# fet_overdrive_v50.net
KiCad netlist of a schematic drawn in EAGLE
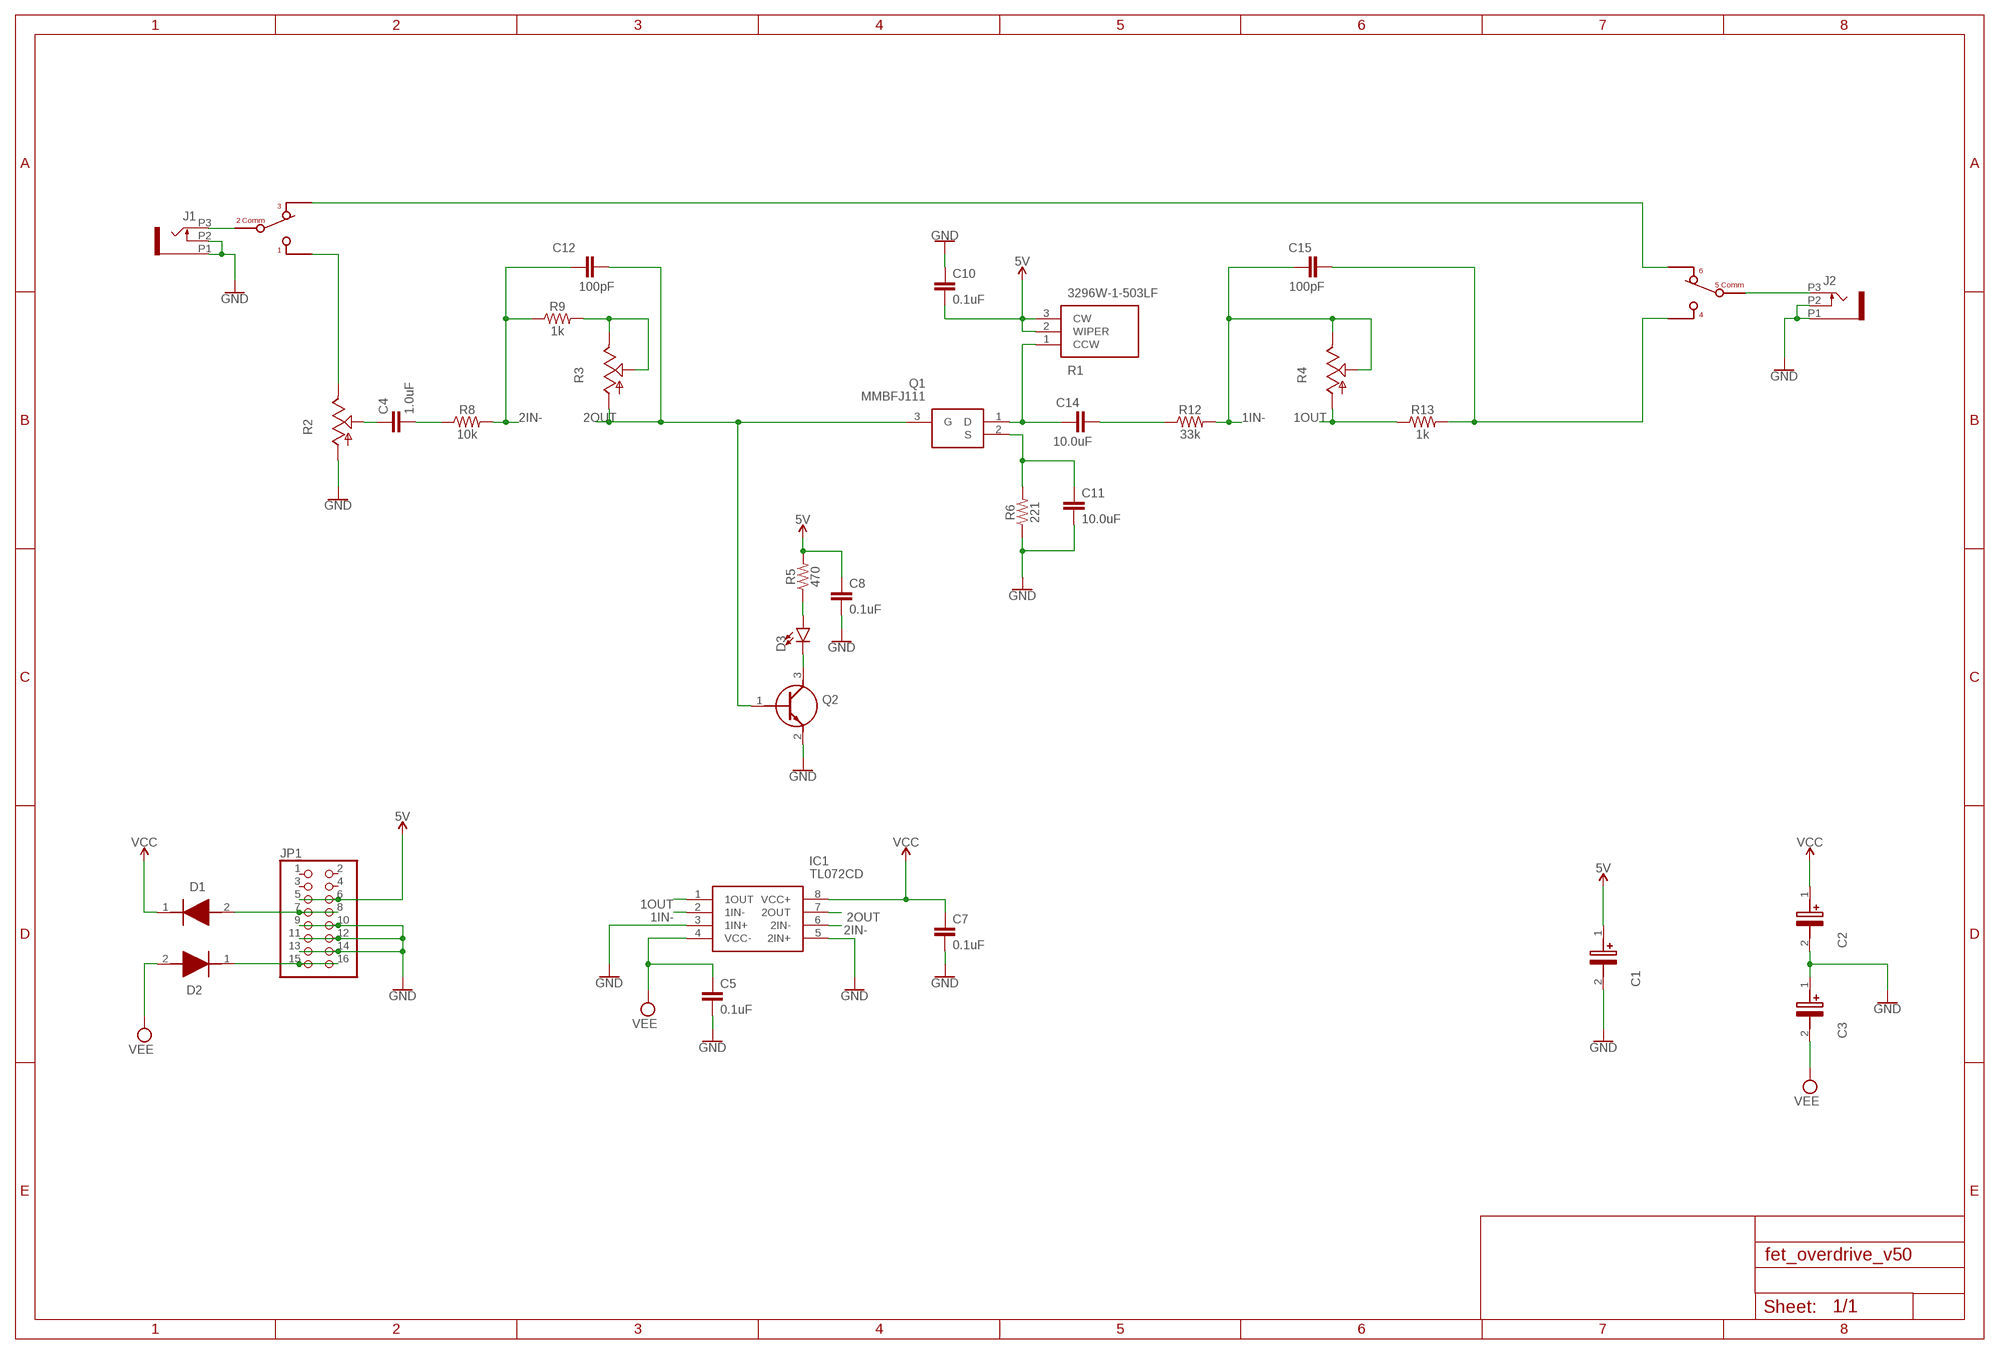
[diagram p0: schematic, sheet 1]

(export (version "E")
  (design (tool "Eeschema 10.0.6"))
  (components
    (comp (ref "C1")
      (value "EEE-FP1E220AR")
      (footprint "eagle-import:EEE0GA101SR")
      (fields (field (name "MOUSER_PART_NUMBER") "667-EEE-FP1E220AR"))
      (libsource (lib "eagle-import") (part "EEE-FP1E220AR"))
    )
    (comp (ref "C2")
      (value "EEE-FK1V470P")
      (footprint "eagle-import:EEE1AA101SP")
      (fields (field (name "MOUSER_PART_NUMBER") "667-EEE-FK1V470P"))
      (libsource (lib "eagle-import") (part "EEE-FK1V470P"))
    )
    (comp (ref "C3")
      (value "EEE-FK1V470P")
      (footprint "eagle-import:EEE1AA101SP")
      (fields (field (name "MOUSER_PART_NUMBER") "667-EEE-FK1V470P"))
      (libsource (lib "eagle-import") (part "EEE-FK1V470P"))
    )
    (comp (ref "C4")
      (value "1.0uF")
      (footprint "eagle-import:0603")
      (libsource (lib "eagle-import") (part "1.0UF-0603-16V-10%"))
    )
    (comp (ref "C5")
      (value "0.1uF")
      (footprint "eagle-import:0603")
      (libsource (lib "eagle-import") (part "0.1UF-0603-25V-5%"))
    )
    (comp (ref "C7")
      (value "0.1uF")
      (footprint "eagle-import:0603")
      (libsource (lib "eagle-import") (part "0.1UF-0603-25V-5%"))
    )
    (comp (ref "C8")
      (value "0.1uF")
      (footprint "eagle-import:0603")
      (libsource (lib "eagle-import") (part "0.1UF-0603-25V-5%"))
    )
    (comp (ref "C10")
      (value "0.1uF")
      (footprint "eagle-import:0603")
      (libsource (lib "eagle-import") (part "0.1UF-0603-25V-5%"))
    )
    (comp (ref "C11")
      (value "10.0uF")
      (footprint "eagle-import:0603")
      (libsource (lib "eagle-import") (part "1.0UF-0603-16V-10%"))
    )
    (comp (ref "C12")
      (value "100pF")
      (footprint "eagle-import:0603")
      (libsource (lib "eagle-import") (part "100PF-0603-50V-5%"))
    )
    (comp (ref "C14")
      (value "10.0uF")
      (footprint "eagle-import:0603")
      (libsource (lib "eagle-import") (part "1.0UF-0603-16V-10%"))
    )
    (comp (ref "C15")
      (value "100pF")
      (footprint "eagle-import:0603")
      (libsource (lib "eagle-import") (part "100PF-0603-50V-5%"))
    )
    (comp (ref "D1")
      (value "1N5819HW-7-F")
      (footprint "eagle-import:SOD3716X145N")
      (fields (field (name "MOUSER_PART_NUMBER") "621-1N5819HW-F"))
      (libsource (lib "eagle-import") (part "1N5819HW-7-F"))
    )
    (comp (ref "D2")
      (value "1N5819HW-7-F")
      (footprint "eagle-import:SOD3716X145N")
      (fields (field (name "MOUSER_PART_NUMBER") "621-1N5819HW-F"))
      (libsource (lib "eagle-import") (part "1N5819HW-7-F"))
    )
    (comp (ref "D3")
      (value "LED3MM")
      (footprint "eagle-import:LED_3MM")
      (libsource (lib "eagle-import") (part "LED3MM"))
    )
    (comp (ref "IC1")
      (value "TL072CD")
      (footprint "eagle-import:SOIC127P600X175-8N")
      (fields (field (name "MOUSER_PART_NUMBER") "595-TL072CD"))
      (libsource (lib "eagle-import") (part "TL072CD"))
    )
    (comp (ref "J1")
      (value "PJ301_THONKICONN6")
      (footprint "eagle-import:WQP_PJ_301M6")
      (libsource (lib "eagle-import") (part "PJ301_THONKICONN6"))
    )
    (comp (ref "J2")
      (value "PJ301_THONKICONN6")
      (footprint "eagle-import:WQP_PJ_301M6")
      (libsource (lib "eagle-import") (part "PJ301_THONKICONN6"))
    )
    (comp (ref "JP1")
      (value "PINHD-2X8")
      (footprint "eagle-import:2X08")
      (libsource (lib "eagle-import") (part "PINHD-2X8"))
    )
    (comp (ref "Q1")
      (value "MMBFJ111")
      (footprint "eagle-import:SOT96P237X111-3N")
      (fields (field (name "MOUSER_PART_NUMBER") "512-MMBFJ111"))
      (libsource (lib "eagle-import") (part "MMBFJ111"))
    )
    (comp (ref "Q2")
      (value "SMMBT3904LT1G")
      (footprint "eagle-import:SOT96P237X111-3N")
      (fields (field (name "MOUSER_PART_NUMBER") "863-SMMBT3904LT1G"))
      (libsource (lib "eagle-import") (part "SMMBT3904LT1G"))
    )
    (comp (ref "R1")
      (value "3296W-1-503LF")
      (footprint "eagle-import:3296W-1")
      (fields (field (name "MOUSER_PART_NUMBER") "652-3296W-1-503LF"))
      (libsource (lib "eagle-import") (part "3296W-1-503LF"))
    )
    (comp (ref "R2")
      (value "POT_USVERTICAL_PS")
      (footprint "eagle-import:ALPS_POT_VERTICAL_PS")
      (libsource (lib "eagle-import") (part "POT_USVERTICAL_PS"))
    )
    (comp (ref "R3")
      (value "POT_USVERTICAL_PS")
      (footprint "eagle-import:ALPS_POT_VERTICAL_PS")
      (libsource (lib "eagle-import") (part "POT_USVERTICAL_PS"))
    )
    (comp (ref "R4")
      (value "POT_USVERTICAL_PS")
      (footprint "eagle-import:ALPS_POT_VERTICAL_PS")
      (libsource (lib "eagle-import") (part "POT_USVERTICAL_PS"))
    )
    (comp (ref "R5")
      (value "470")
      (footprint "eagle-import:0603")
      (libsource (lib "eagle-import") (part "470OHM-0603-1/10W-1%"))
    )
    (comp (ref "R6")
      (value "221")
      (footprint "eagle-import:0603")
      (libsource (lib "eagle-import") (part "1KOHM-0603-1/10W-1%"))
    )
    (comp (ref "R8")
      (value "10k")
      (footprint "eagle-import:0603")
      (libsource (lib "eagle-import") (part "10KOHM-0603-1/10W-1%"))
    )
    (comp (ref "R9")
      (value "1k")
      (footprint "eagle-import:0603")
      (libsource (lib "eagle-import") (part "1KOHM-0603-1/10W-1%"))
    )
    (comp (ref "R12")
      (value "33k")
      (footprint "eagle-import:0603")
      (libsource (lib "eagle-import") (part "33KOHM-0603-1/10W-1%"))
    )
    (comp (ref "R13")
      (value "1k")
      (footprint "eagle-import:0603")
      (libsource (lib "eagle-import") (part "1KOHM-0603-1/10W-1%"))
    )
    (comp (ref "U$2")
      (value "DAILYWELL-DPDT")
      (footprint "eagle-import:DAILYWELL-DPDT")
      (libsource (lib "eagle-import") (part "DAILYWELL-DPDT"))
    )
  )
  (nets
    (net (code "1") (name "/1IN-") (class "Default")
      (node (ref "C15") (pin "1") (pinfunction "1_1") (pintype "passive"))
      (node (ref "IC1") (pin "2") (pinfunction "1IN-_2") (pintype "bidirectional"))
      (node (ref "R12") (pin "2") (pinfunction "2_2") (pintype "passive"))
      (node (ref "R4") (pin "P$1") (pinfunction "E_P$1") (pintype "passive"))
      (node (ref "R4") (pin "P$2") (pinfunction "S_P$2") (pintype "passive"))
    )
    (net (code "2") (name "/1OUT") (class "Default")
      (node (ref "IC1") (pin "1") (pinfunction "1OUT_1") (pintype "bidirectional"))
      (node (ref "R13") (pin "1") (pinfunction "1_1") (pintype "passive"))
      (node (ref "R4") (pin "P$3") (pinfunction "A_P$3") (pintype "passive"))
    )
    (net (code "3") (name "/2IN-") (class "Default")
      (node (ref "C12") (pin "1") (pinfunction "1_1") (pintype "passive"))
      (node (ref "IC1") (pin "6") (pinfunction "2IN-_6") (pintype "bidirectional"))
      (node (ref "R8") (pin "2") (pinfunction "2_2") (pintype "passive"))
      (node (ref "R9") (pin "1") (pinfunction "1_1") (pintype "passive"))
    )
    (net (code "4") (name "/2OUT") (class "Default")
      (node (ref "C12") (pin "2") (pinfunction "2_2") (pintype "passive"))
      (node (ref "IC1") (pin "7") (pinfunction "2OUT_7") (pintype "bidirectional"))
      (node (ref "Q1") (pin "3") (pinfunction "G_3") (pintype "bidirectional"))
      (node (ref "Q2") (pin "1") (pinfunction "B_1") (pintype "bidirectional"))
      (node (ref "R3") (pin "P$3") (pinfunction "A_P$3") (pintype "passive"))
    )
    (net (code "5") (name "5V") (class "Default")
      (node (ref "C1") (pin "1") (pinfunction "+_1") (pintype "bidirectional"))
      (node (ref "C10") (pin "2") (pinfunction "2_2") (pintype "passive"))
      (node (ref "C8") (pin "1") (pinfunction "1_1") (pintype "passive"))
      (node (ref "JP1") (pin "5") (pinfunction "5_5") (pintype "passive"))
      (node (ref "JP1") (pin "6") (pinfunction "6_6") (pintype "passive"))
      (node (ref "R1") (pin "2") (pinfunction "WIPER_2") (pintype "bidirectional"))
      (node (ref "R1") (pin "3") (pinfunction "CW_3") (pintype "bidirectional"))
      (node (ref "R5") (pin "2") (pinfunction "2_2") (pintype "passive"))
    )
    (net (code "6") (name "GND") (class "Default")
      (node (ref "C1") (pin "2") (pinfunction "-_2") (pintype "bidirectional"))
      (node (ref "C10") (pin "1") (pinfunction "1_1") (pintype "passive"))
      (node (ref "C11") (pin "2") (pinfunction "2_2") (pintype "passive"))
      (node (ref "C2") (pin "2") (pinfunction "-_2") (pintype "bidirectional"))
      (node (ref "C3") (pin "1") (pinfunction "+_1") (pintype "bidirectional"))
      (node (ref "C5") (pin "2") (pinfunction "2_2") (pintype "passive"))
      (node (ref "C7") (pin "2") (pinfunction "2_2") (pintype "passive"))
      (node (ref "C8") (pin "2") (pinfunction "2_2") (pintype "passive"))
      (node (ref "IC1") (pin "3") (pinfunction "1IN+_3") (pintype "bidirectional"))
      (node (ref "IC1") (pin "5") (pinfunction "2IN+_5") (pintype "bidirectional"))
      (node (ref "J1") (pin "P1") (pinfunction "1_P1") (pintype "passive"))
      (node (ref "J1") (pin "P2") (pinfunction "2_P2") (pintype "passive"))
      (node (ref "J2") (pin "P1") (pinfunction "1_P1") (pintype "passive"))
      (node (ref "J2") (pin "P2") (pinfunction "2_P2") (pintype "passive"))
      (node (ref "JP1") (pin "10") (pinfunction "10_10") (pintype "passive"))
      (node (ref "JP1") (pin "11") (pinfunction "11_11") (pintype "passive"))
      (node (ref "JP1") (pin "12") (pinfunction "12_12") (pintype "passive"))
      (node (ref "JP1") (pin "13") (pinfunction "13_13") (pintype "passive"))
      (node (ref "JP1") (pin "14") (pinfunction "14_14") (pintype "passive"))
      (node (ref "JP1") (pin "9") (pinfunction "9_9") (pintype "passive"))
      (node (ref "Q2") (pin "2") (pinfunction "E_2") (pintype "bidirectional"))
      (node (ref "R2") (pin "P$3") (pinfunction "A_P$3") (pintype "passive"))
      (node (ref "R6") (pin "1") (pinfunction "1_1") (pintype "passive"))
    )
    (net (code "7") (name "Net-(C4-Pad2)") (class "Default")
      (node (ref "C4") (pin "2") (pinfunction "2_2") (pintype "passive"))
      (node (ref "R8") (pin "1") (pinfunction "1_1") (pintype "passive"))
    )
    (net (code "8") (name "Net-(C14-Pad2)") (class "Default")
      (node (ref "C14") (pin "2") (pinfunction "2_2") (pintype "passive"))
      (node (ref "R12") (pin "1") (pinfunction "1_1") (pintype "passive"))
    )
    (net (code "9") (name "Net-(D1-A)") (class "Default")
      (node (ref "D1") (pin "2") (pinfunction "A_2") (pintype "bidirectional"))
      (node (ref "JP1") (pin "7") (pinfunction "7_7") (pintype "passive"))
      (node (ref "JP1") (pin "8") (pinfunction "8_8") (pintype "passive"))
    )
    (net (code "10") (name "Net-(D2-K)") (class "Default")
      (node (ref "D2") (pin "1") (pinfunction "K_1") (pintype "bidirectional"))
      (node (ref "JP1") (pin "15") (pinfunction "15_15") (pintype "passive"))
      (node (ref "JP1") (pin "16") (pinfunction "16_16") (pintype "passive"))
    )
    (net (code "11") (name "Net-(D3-C)") (class "Default")
      (node (ref "D3") (pin "K") (pinfunction "C_K") (pintype "passive"))
      (node (ref "Q2") (pin "3") (pinfunction "C_3") (pintype "bidirectional"))
    )
    (net (code "12") (name "Net-(D3-PadA)") (class "Default")
      (node (ref "D3") (pin "A") (pinfunction "A_A") (pintype "passive"))
      (node (ref "R5") (pin "1") (pinfunction "1_1") (pintype "passive"))
    )
    (net (code "13") (name "Net-(J1-3)") (class "Default")
      (node (ref "J1") (pin "P3") (pinfunction "3_P3") (pintype "passive"))
      (node (ref "U$2") (pin "P$2") (pinfunction "P$2_P$2") (pintype "bidirectional"))
    )
    (net (code "14") (name "Net-(J2-3)") (class "Default")
      (node (ref "J2") (pin "P3") (pinfunction "3_P3") (pintype "passive"))
      (node (ref "U$2") (pin "P$5") (pinfunction "P$2_P$5") (pintype "bidirectional"))
    )
    (net (code "15") (name "Net-(Q1-D)") (class "Default")
      (node (ref "C14") (pin "1") (pinfunction "1_1") (pintype "passive"))
      (node (ref "Q1") (pin "1") (pinfunction "D_1") (pintype "bidirectional"))
      (node (ref "R1") (pin "1") (pinfunction "CCW_1") (pintype "bidirectional"))
    )
    (net (code "16") (name "Net-(Q1-S)") (class "Default")
      (node (ref "C11") (pin "1") (pinfunction "1_1") (pintype "passive"))
      (node (ref "Q1") (pin "2") (pinfunction "S_2") (pintype "bidirectional"))
      (node (ref "R6") (pin "2") (pinfunction "2_2") (pintype "passive"))
    )
    (net (code "17") (name "Net-(R2-E)") (class "Default")
      (node (ref "R2") (pin "P$1") (pinfunction "E_P$1") (pintype "passive"))
      (node (ref "U$2") (pin "P$1") (pinfunction "P$1_P$1") (pintype "bidirectional"))
    )
    (net (code "18") (name "Net-(R2-S)") (class "Default")
      (node (ref "C4") (pin "1") (pinfunction "1_1") (pintype "passive"))
      (node (ref "R2") (pin "P$2") (pinfunction "S_P$2") (pintype "passive"))
    )
    (net (code "19") (name "Net-(R3-E)") (class "Default")
      (node (ref "R3") (pin "P$1") (pinfunction "E_P$1") (pintype "passive"))
      (node (ref "R3") (pin "P$2") (pinfunction "S_P$2") (pintype "passive"))
      (node (ref "R9") (pin "2") (pinfunction "2_2") (pintype "passive"))
    )
    (net (code "20") (name "Net-(U$2B-P$1)") (class "Default")
      (node (ref "C15") (pin "2") (pinfunction "2_2") (pintype "passive"))
      (node (ref "R13") (pin "2") (pinfunction "2_2") (pintype "passive"))
      (node (ref "U$2") (pin "P$4") (pinfunction "P$1_P$4") (pintype "bidirectional"))
    )
    (net (code "21") (name "Net-(U$2B-P$3)") (class "Default")
      (node (ref "U$2") (pin "P$3") (pinfunction "P$3_P$3") (pintype "bidirectional"))
      (node (ref "U$2") (pin "P$6") (pinfunction "P$3_P$6") (pintype "bidirectional"))
    )
    (net (code "22") (name "VCC") (class "Default")
      (node (ref "C2") (pin "1") (pinfunction "+_1") (pintype "bidirectional"))
      (node (ref "C7") (pin "1") (pinfunction "1_1") (pintype "passive"))
      (node (ref "D1") (pin "1") (pinfunction "K_1") (pintype "bidirectional"))
      (node (ref "IC1") (pin "8") (pinfunction "VCC+_8") (pintype "bidirectional"))
    )
    (net (code "23") (name "VEE") (class "Default")
      (node (ref "C3") (pin "2") (pinfunction "-_2") (pintype "bidirectional"))
      (node (ref "C5") (pin "1") (pinfunction "1_1") (pintype "passive"))
      (node (ref "D2") (pin "2") (pinfunction "A_2") (pintype "bidirectional"))
      (node (ref "IC1") (pin "4") (pinfunction "VCC-_4") (pintype "bidirectional"))
    )
    (net (code "24") (name "unconnected-(JP1-Pad1)") (class "Default")
      (node (ref "JP1") (pin "1") (pinfunction "1_1") (pintype "passive"))
    )
    (net (code "25") (name "unconnected-(JP1-Pad2)") (class "Default")
      (node (ref "JP1") (pin "2") (pinfunction "2_2") (pintype "passive"))
    )
    (net (code "26") (name "unconnected-(JP1-Pad3)") (class "Default")
      (node (ref "JP1") (pin "3") (pinfunction "3_3") (pintype "passive"))
    )
    (net (code "27") (name "unconnected-(JP1-Pad4)") (class "Default")
      (node (ref "JP1") (pin "4") (pinfunction "4_4") (pintype "passive"))
    )
  )
)
